# DiceMC-V1_0.net
KiCad netlist of a schematic drawn in EAGLE
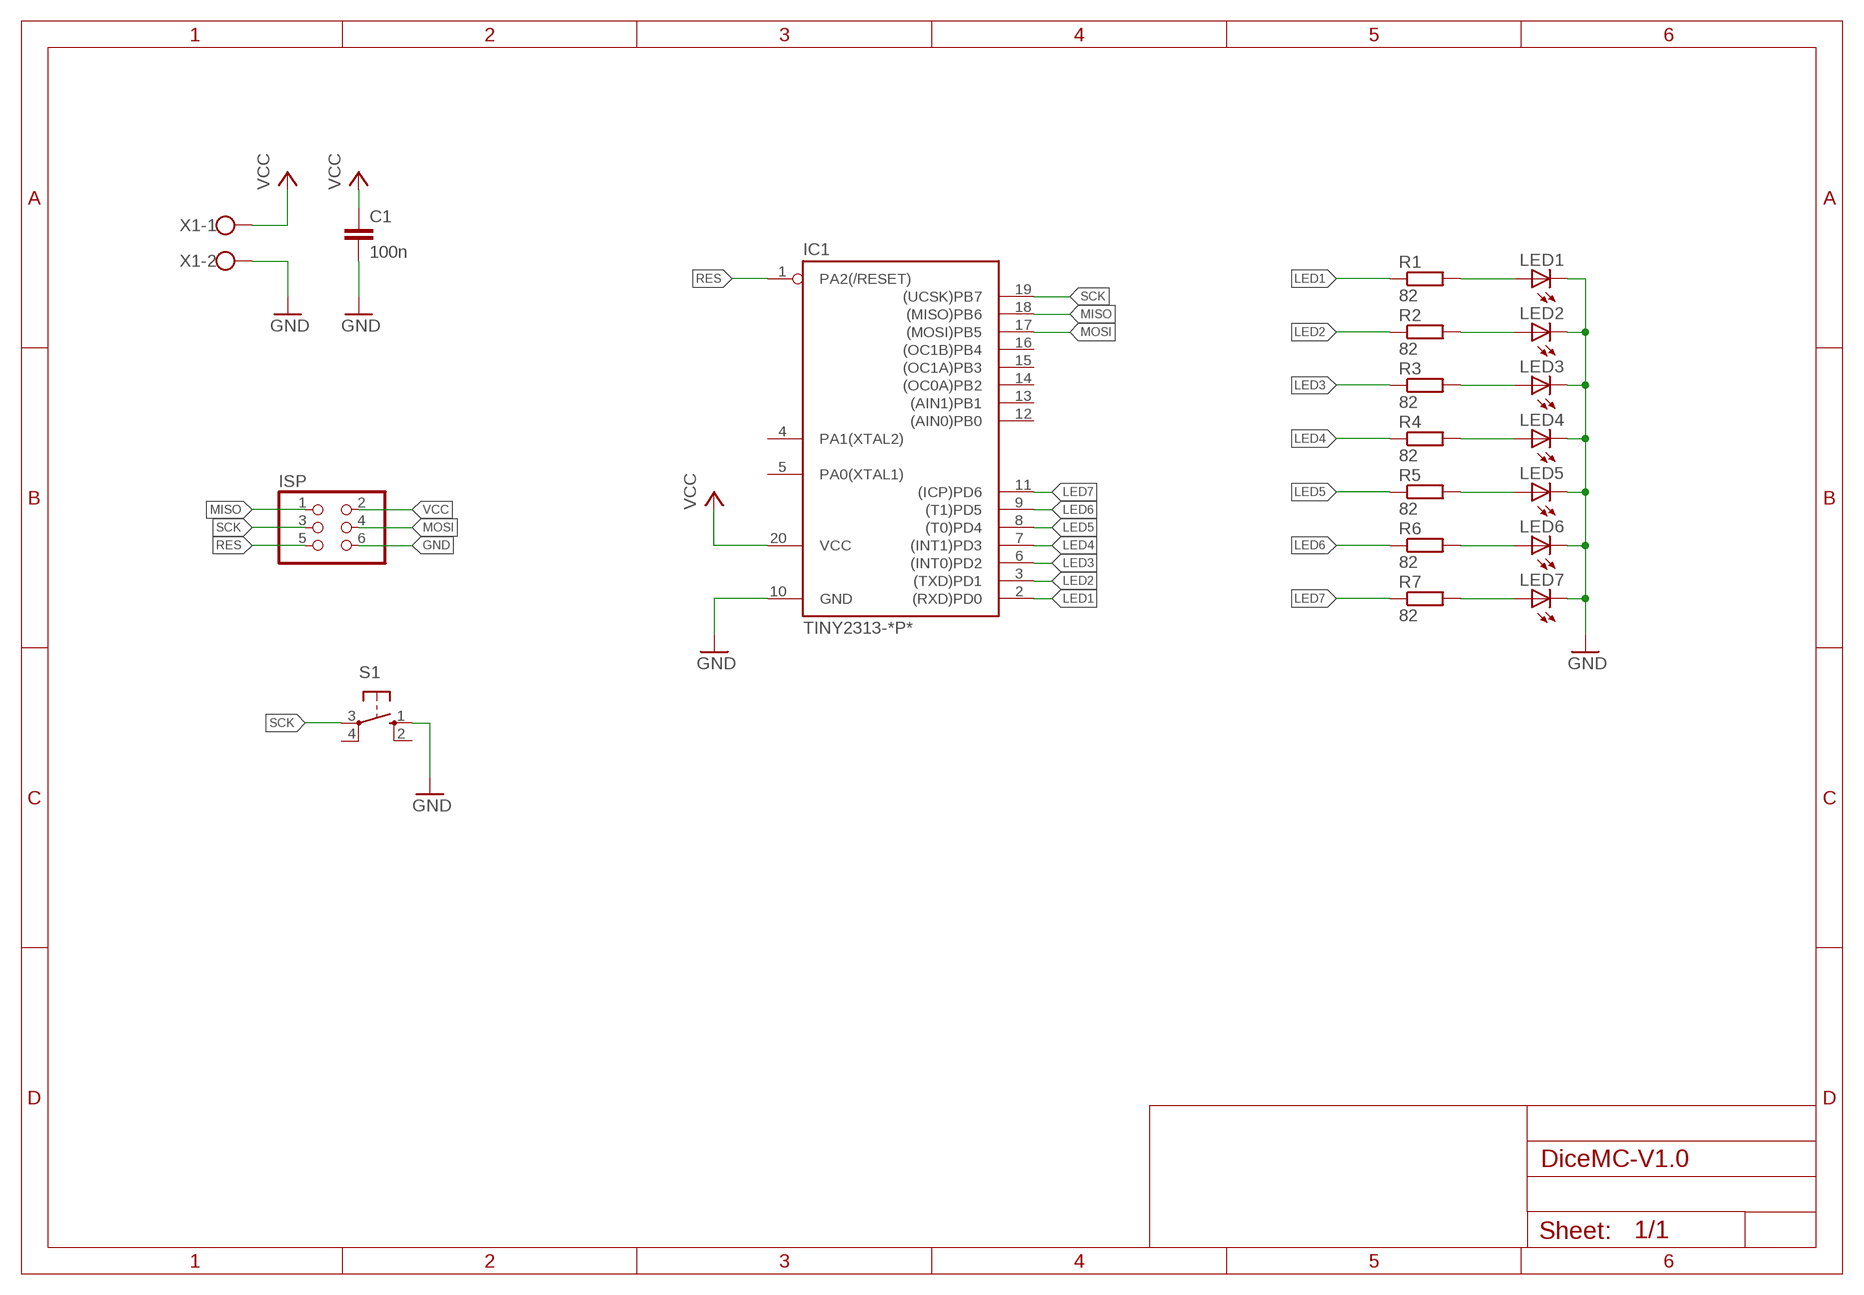
[diagram p0: schematic, sheet 1]

(export (version "E")
  (design (tool "Eeschema 10.0.6"))
  (components
    (comp (ref "C1")
      (value "100n")
      (footprint "eagle-import:C025-025X050")
      (libsource (lib "eagle-import") (part "C-EU025-025X050"))
    )
    (comp (ref "IC1")
      (value "TINY2313-*P*")
      (footprint "eagle-import:DIL20")
      (libsource (lib "eagle-import") (part "TINY2313-P"))
    )
    (comp (ref "ISP")
      (value "PINHD-2X03_2.54")
      (footprint "eagle-import:2X03")
      (libsource (lib "eagle-import") (part "PINHD-2X03_2.54"))
    )
    (comp (ref "LED1")
      (value "LED5MM")
      (footprint "eagle-import:LED5MM")
      (libsource (lib "eagle-import") (part "LED5MM"))
    )
    (comp (ref "LED2")
      (value "LED5MM")
      (footprint "eagle-import:LED5MM")
      (libsource (lib "eagle-import") (part "LED5MM"))
    )
    (comp (ref "LED3")
      (value "LED5MM")
      (footprint "eagle-import:LED5MM")
      (libsource (lib "eagle-import") (part "LED5MM"))
    )
    (comp (ref "LED4")
      (value "LED5MM")
      (footprint "eagle-import:LED5MM")
      (libsource (lib "eagle-import") (part "LED5MM"))
    )
    (comp (ref "LED5")
      (value "LED5MM")
      (footprint "eagle-import:LED5MM")
      (libsource (lib "eagle-import") (part "LED5MM"))
    )
    (comp (ref "LED6")
      (value "LED5MM")
      (footprint "eagle-import:LED5MM")
      (libsource (lib "eagle-import") (part "LED5MM"))
    )
    (comp (ref "LED7")
      (value "LED5MM")
      (footprint "eagle-import:LED5MM")
      (libsource (lib "eagle-import") (part "LED5MM"))
    )
    (comp (ref "R1")
      (value "82")
      (footprint "eagle-import:0207_7")
      (libsource (lib "eagle-import") (part "R-EU_0207/7"))
    )
    (comp (ref "R2")
      (value "82")
      (footprint "eagle-import:0207_7")
      (libsource (lib "eagle-import") (part "R-EU_0207/7"))
    )
    (comp (ref "R3")
      (value "82")
      (footprint "eagle-import:0207_7")
      (libsource (lib "eagle-import") (part "R-EU_0207/7"))
    )
    (comp (ref "R4")
      (value "82")
      (footprint "eagle-import:0207_7")
      (libsource (lib "eagle-import") (part "R-EU_0207/7"))
    )
    (comp (ref "R5")
      (value "82")
      (footprint "eagle-import:0207_7")
      (libsource (lib "eagle-import") (part "R-EU_0207/7"))
    )
    (comp (ref "R6")
      (value "82")
      (footprint "eagle-import:0207_7")
      (libsource (lib "eagle-import") (part "R-EU_0207/7"))
    )
    (comp (ref "R7")
      (value "82")
      (footprint "eagle-import:0207_7")
      (libsource (lib "eagle-import") (part "R-EU_0207/7"))
    )
    (comp (ref "S1")
      (value "10-XX")
      (footprint "eagle-import:B3F-10XX")
      (fields (field (name "MPN") "B3F-1000"))
      (libsource (lib "eagle-import") (part "10-XX"))
    )
    (comp (ref "X1")
      (value "W237-102")
      (footprint "eagle-import:W237-102")
      (fields (field (name "MPN") "237-102"))
      (libsource (lib "eagle-import") (part "W237-102"))
    )
  )
  (nets
    (net (code "1") (name "GND") (class "Default")
      (node (ref "C1") (pin "2") (pinfunction "2_2") (pintype "passive"))
      (node (ref "IC1") (pin "10") (pinfunction "GND_10") (pintype "power_in"))
      (node (ref "ISP") (pin "6") (pinfunction "6_6") (pintype "passive"))
      (node (ref "LED1") (pin "K") (pinfunction "C_K") (pintype "passive"))
      (node (ref "LED2") (pin "K") (pinfunction "C_K") (pintype "passive"))
      (node (ref "LED3") (pin "K") (pinfunction "C_K") (pintype "passive"))
      (node (ref "LED4") (pin "K") (pinfunction "C_K") (pintype "passive"))
      (node (ref "LED5") (pin "K") (pinfunction "C_K") (pintype "passive"))
      (node (ref "LED6") (pin "K") (pinfunction "C_K") (pintype "passive"))
      (node (ref "LED7") (pin "K") (pinfunction "C_K") (pintype "passive"))
      (node (ref "S1") (pin "1") (pinfunction "S_1") (pintype "passive"))
      (node (ref "X1") (pin "2") (pinfunction "KL_2") (pintype "passive"))
    )
    (net (code "2") (name "LED1") (class "Default")
      (node (ref "IC1") (pin "2") (pinfunction "(RXD)PD0_2") (pintype "bidirectional"))
      (node (ref "R1") (pin "1") (pinfunction "1_1") (pintype "passive"))
    )
    (net (code "3") (name "LED2") (class "Default")
      (node (ref "IC1") (pin "3") (pinfunction "(TXD)PD1_3") (pintype "bidirectional"))
      (node (ref "R2") (pin "1") (pinfunction "1_1") (pintype "passive"))
    )
    (net (code "4") (name "LED3") (class "Default")
      (node (ref "IC1") (pin "6") (pinfunction "(INT0)PD2_6") (pintype "bidirectional"))
      (node (ref "R3") (pin "1") (pinfunction "1_1") (pintype "passive"))
    )
    (net (code "5") (name "LED4") (class "Default")
      (node (ref "IC1") (pin "7") (pinfunction "(INT1)PD3_7") (pintype "bidirectional"))
      (node (ref "R4") (pin "1") (pinfunction "1_1") (pintype "passive"))
    )
    (net (code "6") (name "LED5") (class "Default")
      (node (ref "IC1") (pin "8") (pinfunction "(T0)PD4_8") (pintype "bidirectional"))
      (node (ref "R5") (pin "1") (pinfunction "1_1") (pintype "passive"))
    )
    (net (code "7") (name "LED6") (class "Default")
      (node (ref "IC1") (pin "9") (pinfunction "(T1)PD5_9") (pintype "bidirectional"))
      (node (ref "R6") (pin "1") (pinfunction "1_1") (pintype "passive"))
    )
    (net (code "8") (name "LED7") (class "Default")
      (node (ref "IC1") (pin "11") (pinfunction "(ICP)PD6_11") (pintype "bidirectional"))
      (node (ref "R7") (pin "1") (pinfunction "1_1") (pintype "passive"))
    )
    (net (code "9") (name "MISO") (class "Default")
      (node (ref "IC1") (pin "18") (pinfunction "(MISO)PB6_18") (pintype "bidirectional"))
      (node (ref "ISP") (pin "1") (pinfunction "1_1") (pintype "passive"))
    )
    (net (code "10") (name "MOSI") (class "Default")
      (node (ref "IC1") (pin "17") (pinfunction "(MOSI)PB5_17") (pintype "bidirectional"))
      (node (ref "ISP") (pin "4") (pinfunction "4_4") (pintype "passive"))
    )
    (net (code "11") (name "Net-(LED1-PadA)") (class "Default")
      (node (ref "LED1") (pin "A") (pinfunction "A_A") (pintype "passive"))
      (node (ref "R1") (pin "2") (pinfunction "2_2") (pintype "passive"))
    )
    (net (code "12") (name "Net-(LED2-PadA)") (class "Default")
      (node (ref "LED2") (pin "A") (pinfunction "A_A") (pintype "passive"))
      (node (ref "R2") (pin "2") (pinfunction "2_2") (pintype "passive"))
    )
    (net (code "13") (name "Net-(LED3-PadA)") (class "Default")
      (node (ref "LED3") (pin "A") (pinfunction "A_A") (pintype "passive"))
      (node (ref "R3") (pin "2") (pinfunction "2_2") (pintype "passive"))
    )
    (net (code "14") (name "Net-(LED4-PadA)") (class "Default")
      (node (ref "LED4") (pin "A") (pinfunction "A_A") (pintype "passive"))
      (node (ref "R4") (pin "2") (pinfunction "2_2") (pintype "passive"))
    )
    (net (code "15") (name "Net-(LED5-PadA)") (class "Default")
      (node (ref "LED5") (pin "A") (pinfunction "A_A") (pintype "passive"))
      (node (ref "R5") (pin "2") (pinfunction "2_2") (pintype "passive"))
    )
    (net (code "16") (name "Net-(LED6-PadA)") (class "Default")
      (node (ref "LED6") (pin "A") (pinfunction "A_A") (pintype "passive"))
      (node (ref "R6") (pin "2") (pinfunction "2_2") (pintype "passive"))
    )
    (net (code "17") (name "Net-(LED7-PadA)") (class "Default")
      (node (ref "LED7") (pin "A") (pinfunction "A_A") (pintype "passive"))
      (node (ref "R7") (pin "2") (pinfunction "2_2") (pintype "passive"))
    )
    (net (code "18") (name "RES") (class "Default")
      (node (ref "IC1") (pin "1") (pinfunction "PA2(/RESET)_1") (pintype "input"))
      (node (ref "ISP") (pin "5") (pinfunction "5_5") (pintype "passive"))
    )
    (net (code "19") (name "SCK") (class "Default")
      (node (ref "IC1") (pin "19") (pinfunction "(UCSK)PB7_19") (pintype "bidirectional"))
      (node (ref "ISP") (pin "3") (pinfunction "3_3") (pintype "passive"))
      (node (ref "S1") (pin "3") (pinfunction "P_3") (pintype "passive"))
    )
    (net (code "20") (name "VCC") (class "Default")
      (node (ref "C1") (pin "1") (pinfunction "1_1") (pintype "passive"))
      (node (ref "IC1") (pin "20") (pinfunction "VCC_20") (pintype "power_in"))
      (node (ref "ISP") (pin "2") (pinfunction "2_2") (pintype "passive"))
      (node (ref "X1") (pin "1") (pinfunction "KL_1") (pintype "passive"))
    )
    (net (code "21") (name "unconnected-(IC1-(AIN0)PB0-Pad12)") (class "Default")
      (node (ref "IC1") (pin "12") (pinfunction "(AIN0)PB0_12") (pintype "bidirectional"))
    )
    (net (code "22") (name "unconnected-(IC1-(AIN1)PB1-Pad13)") (class "Default")
      (node (ref "IC1") (pin "13") (pinfunction "(AIN1)PB1_13") (pintype "bidirectional"))
    )
    (net (code "23") (name "unconnected-(IC1-(OC0A)PB2-Pad14)") (class "Default")
      (node (ref "IC1") (pin "14") (pinfunction "(OC0A)PB2_14") (pintype "bidirectional"))
    )
    (net (code "24") (name "unconnected-(IC1-(OC1A)PB3-Pad15)") (class "Default")
      (node (ref "IC1") (pin "15") (pinfunction "(OC1A)PB3_15") (pintype "bidirectional"))
    )
    (net (code "25") (name "unconnected-(IC1-(OC1B)PB4-Pad16)") (class "Default")
      (node (ref "IC1") (pin "16") (pinfunction "(OC1B)PB4_16") (pintype "bidirectional"))
    )
    (net (code "26") (name "unconnected-(IC1-PA0(XTAL1)-Pad5)") (class "Default")
      (node (ref "IC1") (pin "5") (pinfunction "PA0(XTAL1)_5") (pintype "bidirectional"))
    )
    (net (code "27") (name "unconnected-(IC1-PA1(XTAL2)-Pad4)") (class "Default")
      (node (ref "IC1") (pin "4") (pinfunction "PA1(XTAL2)_4") (pintype "bidirectional"))
    )
    (net (code "28") (name "unconnected-(S1-P1-Pad4)") (class "Default")
      (node (ref "S1") (pin "4") (pinfunction "P1_4") (pintype "passive"))
    )
    (net (code "29") (name "unconnected-(S1-S1-Pad2)") (class "Default")
      (node (ref "S1") (pin "2") (pinfunction "S1_2") (pintype "passive"))
    )
  )
)
